# ETH_HMI.net
KiCad netlist of a schematic drawn in Altium Designer
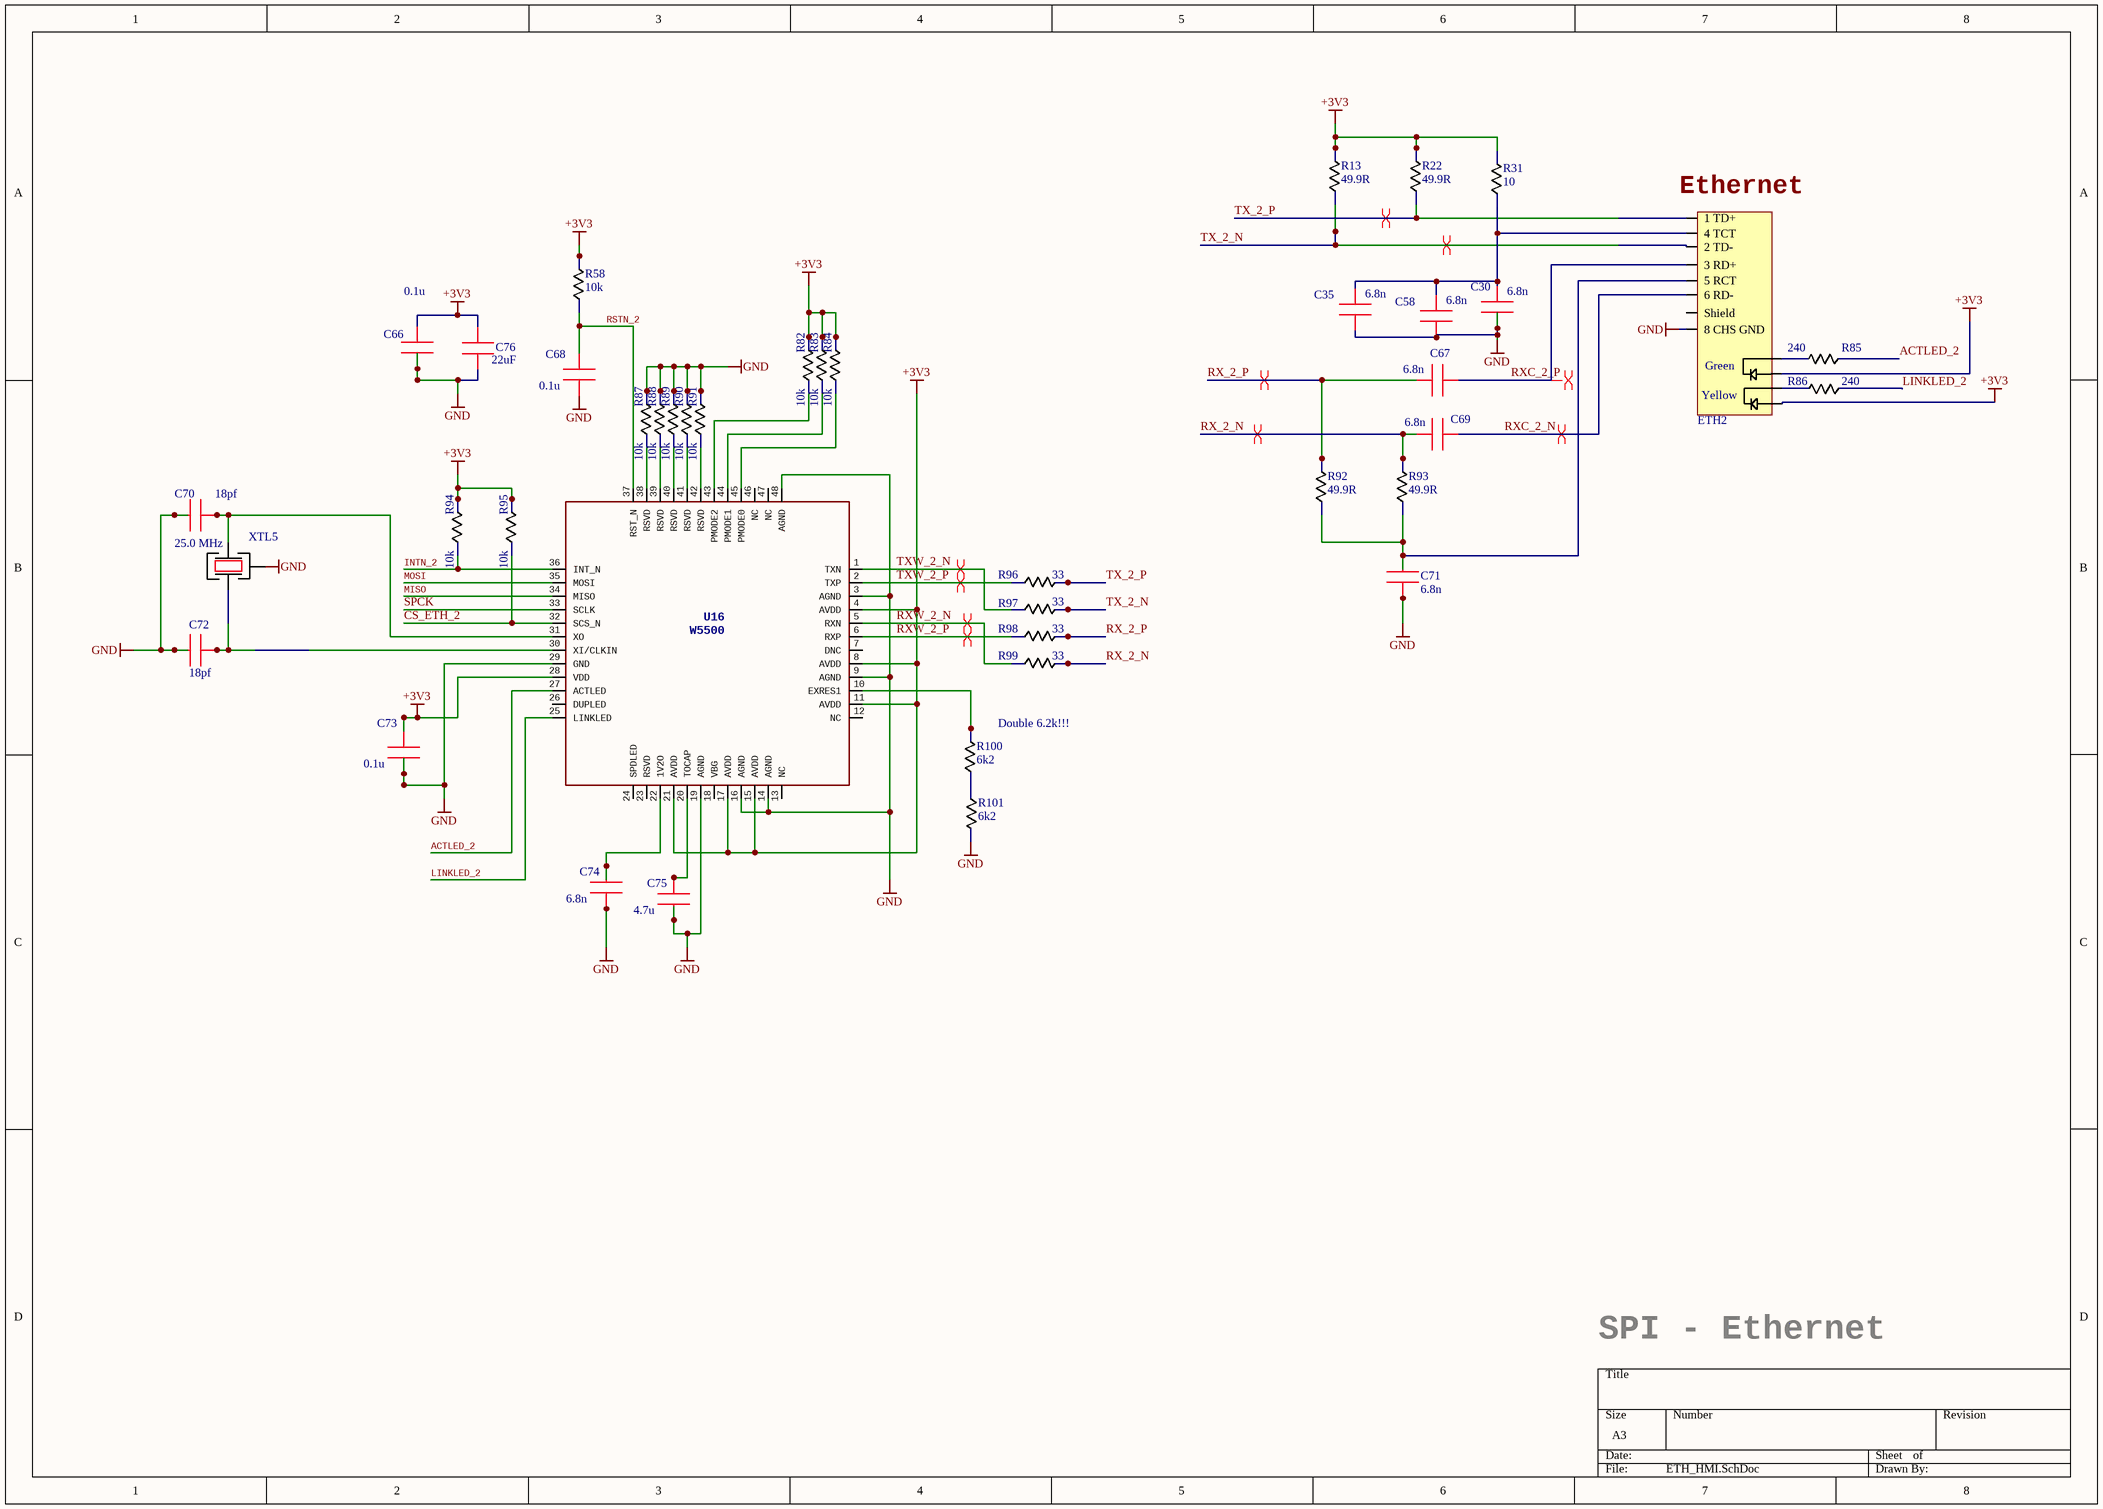
[diagram p0: ETH_HMI.SchDoc]

(export (version "E")
  (design (tool "Eeschema 10.0.6"))
  (components
    (comp (ref "C30")
      (value "6.8n")
      (footprint "0603 CAP")
      (description "GRM188R71H223KA01D")
      (libsource (lib "kontr") (part "0603 CAP"))
    )
    (comp (ref "C35")
      (value "6.8n")
      (footprint "0603 CAP")
      (description "GRM188R71H223KA01D")
      (libsource (lib "kontr") (part "0603 CAP"))
    )
    (comp (ref "C58")
      (value "6.8n")
      (footprint "0603 CAP")
      (description "GRM188R71H223KA01D")
      (libsource (lib "kontr") (part "0603 CAP"))
    )
    (comp (ref "C66")
      (value "0.1u")
      (footprint "0603 CAP")
      (description "GRM188R71E104KA01D")
      (libsource (lib "kontr") (part "0603 CAP"))
    )
    (comp (ref "C67")
      (value "6.8n")
      (footprint "0603 CAP")
      (description "CC0603KRX7R9BB682")
      (libsource (lib "") (part "0603 CAP_1"))
    )
    (comp (ref "C68")
      (value "0.1u")
      (footprint "0603 CAP")
      (description "GRM188R71E104KA01D")
      (libsource (lib "kontr") (part "0603 CAP"))
    )
    (comp (ref "C69")
      (value "6.8n")
      (footprint "0603 CAP")
      (description "CC0603KRX7R9BB682")
      (libsource (lib "") (part "0603 CAP_1"))
    )
    (comp (ref "C70")
      (value "18pf")
      (footprint "0603 CAP")
      (description "GRM1885C1H180JA01D")
      (libsource (lib "") (part "0603 CAP_1"))
    )
    (comp (ref "C71") (value "6.8n") (footprint "0603 CAP") (libsource (lib "kontr") (part "0603 CAP")))
    (comp (ref "C72")
      (value "18pf")
      (footprint "0603 CAP")
      (description "GRM1885C1H180JA01D")
      (libsource (lib "") (part "0603 CAP_1"))
    )
    (comp (ref "C73")
      (value "0.1u")
      (footprint "0603 CAP")
      (description "GRM188R71E104KA01D")
      (libsource (lib "kontr") (part "0603 CAP"))
    )
    (comp (ref "C74") (value "6.8n") (footprint "0603 CAP") (libsource (lib "kontr") (part "0603 CAP")))
    (comp (ref "C75")
      (value "4.7u")
      (footprint "0603 CAP")
      (description "GRM188R61A475KE15D")
      (libsource (lib "kontr") (part "0603 CAP"))
    )
    (comp (ref "C76")
      (value "22uF")
      (footprint "CAP CER 1210 NP")
      (description "CC1210KKX5R7BB226")
      (libsource (lib "kontr") (part "0805 Cap"))
    )
    (comp (ref "ETH2")
      (value "ETH?")
      (footprint "J011D21BNL")
      (description "J0011D21BNL")
      (libsource (lib "kontr") (part "J0011D21BNL"))
    )
    (comp (ref "R13")
      (value "49.9R")
      (footprint "0603 - RES")
      (description "RC0603FR-0749R9")
      (libsource (lib "kontr") (part "0603 RES"))
    )
    (comp (ref "R22")
      (value "49.9R")
      (footprint "0603 - RES")
      (description "RC0603FR-0749R9")
      (libsource (lib "kontr") (part "0603 RES"))
    )
    (comp (ref "R31")
      (value "10")
      (footprint "0603 - RES")
      (description "CRCW060310R0FKEA")
      (libsource (lib "kontr") (part "0603 RES"))
    )
    (comp (ref "R58")
      (value "10k")
      (footprint "0603 - RES")
      (description "RC0603JR-0710K")
      (libsource (lib "kontr") (part "0603 RES"))
    )
    (comp (ref "R82")
      (value "10k")
      (footprint "0603 - RES")
      (description "RC0603JR-0710K")
      (libsource (lib "kontr") (part "0603 RES"))
    )
    (comp (ref "R83")
      (value "10k")
      (footprint "0603 - RES")
      (description "RC0603JR-0710K")
      (libsource (lib "kontr") (part "0603 RES"))
    )
    (comp (ref "R84")
      (value "10k")
      (footprint "0603 - RES")
      (description "RC0603JR-0710K")
      (libsource (lib "kontr") (part "0603 RES"))
    )
    (comp (ref "R85")
      (value "240")
      (footprint "0603 - RES")
      (description "CRCW060310R0FKEA")
      (libsource (lib "kontr") (part "0603 RES"))
    )
    (comp (ref "R86")
      (value "240")
      (footprint "0603 - RES")
      (description "CRCW060310R0FKEA")
      (libsource (lib "kontr") (part "0603 RES"))
    )
    (comp (ref "R87")
      (value "10k")
      (footprint "0603 - RES")
      (description "RC0603JR-0710K")
      (libsource (lib "kontr") (part "0603 RES"))
    )
    (comp (ref "R88")
      (value "10k")
      (footprint "0603 - RES")
      (description "RC0603JR-0710K")
      (libsource (lib "kontr") (part "0603 RES"))
    )
    (comp (ref "R89")
      (value "10k")
      (footprint "0603 - RES")
      (description "RC0603JR-0710K")
      (libsource (lib "kontr") (part "0603 RES"))
    )
    (comp (ref "R90")
      (value "10k")
      (footprint "0603 - RES")
      (description "RC0603JR-0710K")
      (libsource (lib "kontr") (part "0603 RES"))
    )
    (comp (ref "R91")
      (value "10k")
      (footprint "0603 - RES")
      (description "RC0603JR-0710K")
      (libsource (lib "kontr") (part "0603 RES"))
    )
    (comp (ref "R92")
      (value "49.9R")
      (footprint "0603 - RES")
      (description "RC0603FR-0749R9")
      (libsource (lib "kontr") (part "0603 RES"))
    )
    (comp (ref "R93")
      (value "49.9R")
      (footprint "0603 - RES")
      (description "RC0603FR-0749R9")
      (libsource (lib "kontr") (part "0603 RES"))
    )
    (comp (ref "R94")
      (value "10k")
      (footprint "0603 - RES")
      (description "RC0603JR-0710K")
      (libsource (lib "kontr") (part "0603 RES"))
    )
    (comp (ref "R95")
      (value "10k")
      (footprint "0603 - RES")
      (description "RC0603JR-0710K")
      (libsource (lib "kontr") (part "0603 RES"))
    )
    (comp (ref "R96")
      (value "33")
      (footprint "0603 - RES")
      (description "RC0603FR-0733R")
      (libsource (lib "kontr") (part "0603 RES"))
    )
    (comp (ref "R97")
      (value "33")
      (footprint "0603 - RES")
      (description "RC0603FR-0733R")
      (libsource (lib "kontr") (part "0603 RES"))
    )
    (comp (ref "R98")
      (value "33")
      (footprint "0603 - RES")
      (description "RC0603FR-0733R")
      (libsource (lib "kontr") (part "0603 RES"))
    )
    (comp (ref "R99")
      (value "33")
      (footprint "0603 - RES")
      (description "RC0603FR-0733R")
      (libsource (lib "kontr") (part "0603 RES"))
    )
    (comp (ref "R100")
      (value "6k2")
      (footprint "0603 - RES")
      (description "RC0603FR-076K2")
      (libsource (lib "kontr") (part "0603 RES"))
    )
    (comp (ref "R101")
      (value "6k2")
      (footprint "0603 - RES")
      (description "0805 SMD Resistor")
      (libsource (lib "kontr") (part "Resistor 0805"))
    )
    (comp (ref "U16") (value "W5500") (footprint "LQFP 48") (libsource (lib "W5500") (part "W5500")))
    (comp (ref "XTL5")
      (value "25.0 MHz")
      (footprint "XTAL KX-7T")
      (description "Geyer KX-7 25.0 MHz")
      (libsource (lib "PLC M3") (part "KX-7"))
    )
  )
  (nets
    (net (code "1") (name "+3V3") (class "Default")
      (node (ref "C66") (pin "1") (pinfunction "1_1") (pintype "passive"))
      (node (ref "C73") (pin "1") (pinfunction "1_1") (pintype "passive"))
      (node (ref "C76") (pin "2") (pinfunction "2_2") (pintype "passive"))
      (node (ref "ETH2") (pin "12") (pinfunction "LDYE_12") (pintype "passive"))
      (node (ref "ETH2") (pin "9") (pinfunction "LDGr_9") (pintype "passive"))
      (node (ref "R13") (pin "2") (pintype "passive"))
      (node (ref "R22") (pin "2") (pintype "passive"))
      (node (ref "R31") (pin "2") (pintype "passive"))
      (node (ref "R58") (pin "2") (pintype "passive"))
      (node (ref "R82") (pin "2") (pintype "passive"))
      (node (ref "R83") (pin "2") (pintype "passive"))
      (node (ref "R84") (pin "2") (pintype "passive"))
      (node (ref "R94") (pin "2") (pintype "passive"))
      (node (ref "R95") (pin "2") (pintype "passive"))
      (node (ref "U16") (pin "11") (pinfunction "AVDD_11") (pintype "passive"))
      (node (ref "U16") (pin "15") (pinfunction "AVDD_15") (pintype "passive"))
      (node (ref "U16") (pin "17") (pinfunction "AVDD_17") (pintype "passive"))
      (node (ref "U16") (pin "21") (pinfunction "AVDD_21") (pintype "passive"))
      (node (ref "U16") (pin "28") (pinfunction "VDD_28") (pintype "passive"))
      (node (ref "U16") (pin "4") (pinfunction "AVDD_4") (pintype "passive"))
      (node (ref "U16") (pin "8") (pinfunction "AVDD_8") (pintype "passive"))
    )
    (net (code "2") (name "/ACTLED_2") (class "Default")
      (node (ref "R85") (pin "1") (pintype "passive"))
      (node (ref "U16") (pin "27") (pinfunction "ACTLED_27") (pintype "passive"))
    )
    (net (code "3") (name "/CS_ETH_2") (class "Default")
      (node (ref "R95") (pin "1") (pintype "passive"))
      (node (ref "U16") (pin "32") (pinfunction "SCS_N_32") (pintype "passive"))
    )
    (net (code "4") (name "/INTN_2") (class "Default")
      (node (ref "R94") (pin "1") (pintype "passive"))
      (node (ref "U16") (pin "36") (pinfunction "INT_N_36") (pintype "passive"))
    )
    (net (code "5") (name "/LINKLED_2") (class "Default")
      (node (ref "R86") (pin "1") (pintype "passive"))
      (node (ref "U16") (pin "25") (pinfunction "LINKLED_25") (pintype "passive"))
    )
    (net (code "6") (name "/MISO") (class "Default")
      (node (ref "U16") (pin "34") (pinfunction "MISO_34") (pintype "passive"))
    )
    (net (code "7") (name "/MOSI") (class "Default")
      (node (ref "U16") (pin "35") (pinfunction "MOSI_35") (pintype "passive"))
    )
    (net (code "8") (name "/RSTN_2") (class "Default")
      (node (ref "C68") (pin "1") (pinfunction "1_1") (pintype "passive"))
      (node (ref "R58") (pin "1") (pintype "passive"))
      (node (ref "U16") (pin "37") (pinfunction "RST_N_37") (pintype "passive"))
    )
    (net (code "9") (name "/RXC_2_N") (class "Default")
      (node (ref "C69") (pin "2") (pinfunction "2_2") (pintype "passive"))
      (node (ref "ETH2") (pin "6") (pinfunction "6_RD-_6") (pintype "passive"))
    )
    (net (code "10") (name "/RXC_2_P") (class "Default")
      (node (ref "C67") (pin "2") (pinfunction "2_2") (pintype "passive"))
      (node (ref "ETH2") (pin "3") (pinfunction "3_RD+_3") (pintype "passive"))
    )
    (net (code "11") (name "/RXW_2_N") (class "Default")
      (node (ref "R99") (pin "1") (pintype "passive"))
      (node (ref "U16") (pin "5") (pinfunction "RXN_5") (pintype "passive"))
    )
    (net (code "12") (name "/RXW_2_P") (class "Default")
      (node (ref "R98") (pin "1") (pintype "passive"))
      (node (ref "U16") (pin "6") (pinfunction "RXP_6") (pintype "passive"))
    )
    (net (code "13") (name "/RX_2_N") (class "Default")
      (node (ref "C69") (pin "1") (pinfunction "1_1") (pintype "passive"))
      (node (ref "R93") (pin "2") (pintype "passive"))
      (node (ref "R99") (pin "2") (pintype "passive"))
    )
    (net (code "14") (name "/RX_2_P") (class "Default")
      (node (ref "C67") (pin "1") (pinfunction "1_1") (pintype "passive"))
      (node (ref "R92") (pin "2") (pintype "passive"))
      (node (ref "R98") (pin "2") (pintype "passive"))
    )
    (net (code "15") (name "/SPCK") (class "Default")
      (node (ref "U16") (pin "33") (pinfunction "SCLK_33") (pintype "passive"))
    )
    (net (code "16") (name "/TXW_2_N") (class "Default")
      (node (ref "R97") (pin "1") (pintype "passive"))
      (node (ref "U16") (pin "1") (pinfunction "TXN_1") (pintype "passive"))
    )
    (net (code "17") (name "/TXW_2_P") (class "Default")
      (node (ref "R96") (pin "1") (pintype "passive"))
      (node (ref "U16") (pin "2") (pinfunction "TXP_2") (pintype "passive"))
    )
    (net (code "18") (name "/TX_2_N") (class "Default")
      (node (ref "ETH2") (pin "2") (pinfunction "2_TD-_2") (pintype "passive"))
      (node (ref "R13") (pin "1") (pintype "passive"))
      (node (ref "R97") (pin "2") (pintype "passive"))
    )
    (net (code "19") (name "/TX_2_P") (class "Default")
      (node (ref "ETH2") (pin "1") (pinfunction "1_TD+_1") (pintype "passive"))
      (node (ref "R22") (pin "1") (pintype "passive"))
      (node (ref "R96") (pin "2") (pintype "passive"))
    )
    (net (code "20") (name "GND") (class "Default")
      (node (ref "C30") (pin "2") (pinfunction "2_2") (pintype "passive"))
      (node (ref "C35") (pin "2") (pinfunction "2_2") (pintype "passive"))
      (node (ref "C58") (pin "2") (pinfunction "2_2") (pintype "passive"))
      (node (ref "C66") (pin "2") (pinfunction "2_2") (pintype "passive"))
      (node (ref "C68") (pin "2") (pinfunction "2_2") (pintype "passive"))
      (node (ref "C70") (pin "1") (pinfunction "1_1") (pintype "passive"))
      (node (ref "C71") (pin "2") (pinfunction "2_2") (pintype "passive"))
      (node (ref "C72") (pin "1") (pinfunction "1_1") (pintype "passive"))
      (node (ref "C73") (pin "2") (pinfunction "2_2") (pintype "passive"))
      (node (ref "C74") (pin "2") (pinfunction "2_2") (pintype "passive"))
      (node (ref "C75") (pin "2") (pinfunction "2_2") (pintype "passive"))
      (node (ref "C76") (pin "1") (pinfunction "1_1") (pintype "passive"))
      (node (ref "ETH2") (pin "8") (pinfunction "8_CHS_GND_8") (pintype "passive"))
      (node (ref "R101") (pin "2") (pintype "passive"))
      (node (ref "R87") (pin "2") (pintype "passive"))
      (node (ref "R88") (pin "2") (pintype "passive"))
      (node (ref "R89") (pin "2") (pintype "passive"))
      (node (ref "R90") (pin "2") (pintype "passive"))
      (node (ref "R91") (pin "2") (pintype "passive"))
      (node (ref "U16") (pin "14") (pinfunction "AGND_14") (pintype "passive"))
      (node (ref "U16") (pin "16") (pinfunction "AGND_16") (pintype "passive"))
      (node (ref "U16") (pin "19") (pinfunction "AGND_19") (pintype "passive"))
      (node (ref "U16") (pin "29") (pinfunction "GND_29") (pintype "passive"))
      (node (ref "U16") (pin "3") (pinfunction "AGND_3") (pintype "passive"))
      (node (ref "U16") (pin "48") (pinfunction "AGND_48") (pintype "passive"))
      (node (ref "U16") (pin "9") (pinfunction "AGND_9") (pintype "passive"))
      (node (ref "XTL5") (pin "2") (pinfunction "2_2") (pintype "passive"))
    )
    (net (code "21") (name "Net-(ETH2-4_TCT)") (class "Default")
      (node (ref "C30") (pin "1") (pinfunction "1_1") (pintype "passive"))
      (node (ref "C35") (pin "1") (pinfunction "1_1") (pintype "passive"))
      (node (ref "C58") (pin "1") (pinfunction "1_1") (pintype "passive"))
      (node (ref "ETH2") (pin "4") (pinfunction "4_TCT_4") (pintype "passive"))
      (node (ref "R31") (pin "1") (pintype "passive"))
    )
    (net (code "22") (name "Net-(ETH2-5_RCT)") (class "Default")
      (node (ref "C71") (pin "1") (pinfunction "1_1") (pintype "passive"))
      (node (ref "ETH2") (pin "5") (pinfunction "5_RCT_5") (pintype "passive"))
      (node (ref "R92") (pin "1") (pintype "passive"))
      (node (ref "R93") (pin "1") (pintype "passive"))
    )
    (net (code "23") (name "Net-(ETH2-LDGr-Pad10)") (class "Default")
      (node (ref "ETH2") (pin "10") (pinfunction "LDGr_10") (pintype "passive"))
      (node (ref "R85") (pin "2") (pintype "passive"))
    )
    (net (code "24") (name "Net-(ETH2-LDYE-Pad11)") (class "Default")
      (node (ref "ETH2") (pin "11") (pinfunction "LDYE_11") (pintype "passive"))
      (node (ref "R86") (pin "2") (pintype "passive"))
    )
    (net (code "25") (name "Net-(R87-Pad1)") (class "Default")
      (node (ref "R87") (pin "1") (pintype "passive"))
      (node (ref "U16") (pin "38") (pinfunction "RSVD_38") (pintype "passive"))
    )
    (net (code "26") (name "Net-(R88-Pad1)") (class "Default")
      (node (ref "R88") (pin "1") (pintype "passive"))
      (node (ref "U16") (pin "39") (pinfunction "RSVD_39") (pintype "passive"))
    )
    (net (code "27") (name "Net-(R89-Pad1)") (class "Default")
      (node (ref "R89") (pin "1") (pintype "passive"))
      (node (ref "U16") (pin "40") (pinfunction "RSVD_40") (pintype "passive"))
    )
    (net (code "28") (name "Net-(R90-Pad1)") (class "Default")
      (node (ref "R90") (pin "1") (pintype "passive"))
      (node (ref "U16") (pin "41") (pinfunction "RSVD_41") (pintype "passive"))
    )
    (net (code "29") (name "Net-(R91-Pad1)") (class "Default")
      (node (ref "R91") (pin "1") (pintype "passive"))
      (node (ref "U16") (pin "42") (pinfunction "RSVD_42") (pintype "passive"))
    )
    (net (code "30") (name "Net-(R100-Pad1)") (class "Default")
      (node (ref "R100") (pin "1") (pintype "passive"))
      (node (ref "R101") (pin "1") (pintype "passive"))
    )
    (net (code "31") (name "Net-(U16-1V2O)") (class "Default")
      (node (ref "C74") (pin "1") (pinfunction "1_1") (pintype "passive"))
      (node (ref "U16") (pin "22") (pinfunction "1V2O_22") (pintype "passive"))
    )
    (net (code "32") (name "Net-(U16-EXRES1)") (class "Default")
      (node (ref "R100") (pin "2") (pintype "passive"))
      (node (ref "U16") (pin "10") (pinfunction "EXRES1_10") (pintype "passive"))
    )
    (net (code "33") (name "Net-(U16-PMODE0)") (class "Default")
      (node (ref "R84") (pin "1") (pintype "passive"))
      (node (ref "U16") (pin "45") (pinfunction "PMODE0_45") (pintype "passive"))
    )
    (net (code "34") (name "Net-(U16-PMODE1)") (class "Default")
      (node (ref "R83") (pin "1") (pintype "passive"))
      (node (ref "U16") (pin "44") (pinfunction "PMODE1_44") (pintype "passive"))
    )
    (net (code "35") (name "Net-(U16-PMODE2)") (class "Default")
      (node (ref "R82") (pin "1") (pintype "passive"))
      (node (ref "U16") (pin "43") (pinfunction "PMODE2_43") (pintype "passive"))
    )
    (net (code "36") (name "Net-(U16-TOCAP)") (class "Default")
      (node (ref "C75") (pin "1") (pinfunction "1_1") (pintype "passive"))
      (node (ref "U16") (pin "20") (pinfunction "TOCAP_20") (pintype "passive"))
    )
    (net (code "37") (name "Net-(U16-XI{slash}CLKIN)") (class "Default")
      (node (ref "C72") (pin "2") (pinfunction "2_2") (pintype "passive"))
      (node (ref "U16") (pin "30") (pinfunction "XI/CLKIN_30") (pintype "passive"))
      (node (ref "XTL5") (pin "1") (pinfunction "5_1") (pintype "passive"))
    )
    (net (code "38") (name "Net-(U16-XO)") (class "Default")
      (node (ref "C70") (pin "2") (pinfunction "2_2") (pintype "passive"))
      (node (ref "U16") (pin "31") (pinfunction "XO_31") (pintype "passive"))
      (node (ref "XTL5") (pin "3") (pinfunction "5_3") (pintype "passive"))
    )
    (net (code "39") (name "unconnected-(ETH2-Shield-PadSHIELD)") (class "Default")
      (node (ref "ETH2") (pin "SHIELD") (pinfunction "Shield_SHIELD") (pintype "passive"))
    )
    (net (code "40") (name "unconnected-(U16-DNC-Pad7)") (class "Default")
      (node (ref "U16") (pin "7") (pinfunction "DNC_7") (pintype "passive"))
    )
    (net (code "41") (name "unconnected-(U16-DUPLED-Pad26)") (class "Default")
      (node (ref "U16") (pin "26") (pinfunction "DUPLED_26") (pintype "passive"))
    )
    (net (code "42") (name "unconnected-(U16-NC-Pad12)") (class "Default")
      (node (ref "U16") (pin "12") (pinfunction "NC_12") (pintype "passive"))
    )
    (net (code "43") (name "unconnected-(U16-NC-Pad13)") (class "Default")
      (node (ref "U16") (pin "13") (pinfunction "NC_13") (pintype "passive"))
    )
    (net (code "44") (name "unconnected-(U16-NC-Pad46)") (class "Default")
      (node (ref "U16") (pin "46") (pinfunction "NC_46") (pintype "passive"))
    )
    (net (code "45") (name "unconnected-(U16-NC-Pad47)") (class "Default")
      (node (ref "U16") (pin "47") (pinfunction "NC_47") (pintype "passive"))
    )
    (net (code "46") (name "unconnected-(U16-RSVD-Pad23)") (class "Default")
      (node (ref "U16") (pin "23") (pinfunction "RSVD_23") (pintype "passive"))
    )
    (net (code "47") (name "unconnected-(U16-SPDLED-Pad24)") (class "Default")
      (node (ref "U16") (pin "24") (pinfunction "SPDLED_24") (pintype "passive"))
    )
    (net (code "48") (name "unconnected-(U16-VBG-Pad18)") (class "Default")
      (node (ref "U16") (pin "18") (pinfunction "VBG_18") (pintype "passive"))
    )
  )
)
